# 1__Power.net
KiCad netlist of a schematic drawn in Altium Designer
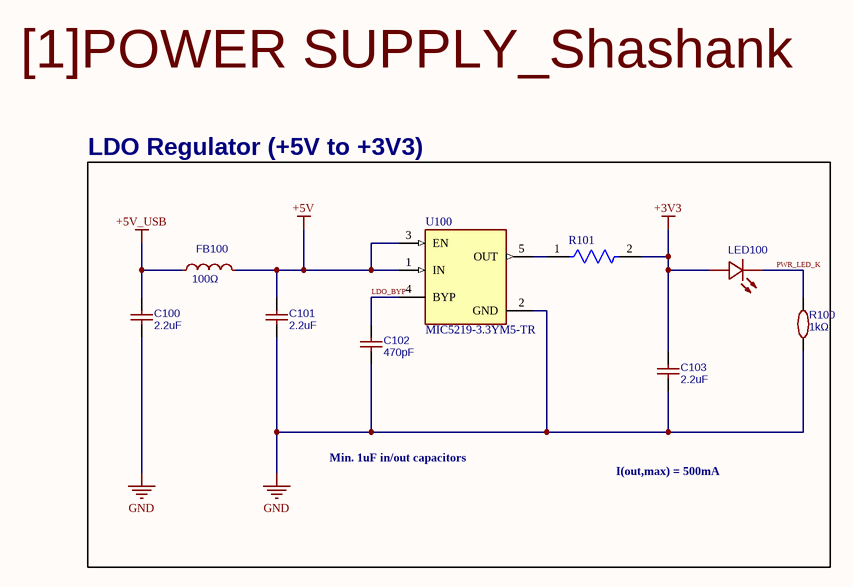
[diagram p0: [1]_Power.SchDoc]

(export (version "E")
  (design (tool "Eeschema 10.0.6"))
  (components
    (comp (ref "C100")
      (value "2.2uF")
      (footprint "C0603")
      (fields
        (field (name "MANUFACTURER PART") "CL10A225KO8NNNC")
        (field (name "MANUFACTURER") "SAMSUNG(三星)")
      )
      (libsource (lib "Power_Lib") (part "2.2uF"))
    )
    (comp (ref "C101")
      (value "2.2uF")
      (footprint "C0603")
      (fields
        (field (name "MANUFACTURER PART") "CL10A225KO8NNNC")
        (field (name "MANUFACTURER") "SAMSUNG(三星)")
      )
      (libsource (lib "Power_Lib") (part "2.2uF"))
    )
    (comp (ref "C102")
      (value "470pF")
      (footprint "C0402")
      (fields (field (name "MANUFACTURER") "FH(风华)") (field (name "MANUFACTURER PART") "0402B471K500NT"))
      (libsource (lib "Power_Lib") (part "470pF"))
    )
    (comp (ref "C103")
      (value "2.2uF")
      (footprint "C0603")
      (fields
        (field (name "MANUFACTURER PART") "CL10A225KO8NNNC")
        (field (name "MANUFACTURER") "SAMSUNG(三星)")
      )
      (libsource (lib "Power_Lib") (part "2.2uF"))
    )
    (comp (ref "FB100")
      (value "100Ω")
      (footprint "L0603")
      (fields
        (field (name "MANUFACTURER") "Sunlord(顺络)")
        (field (name "MANUFACTURER PART") "PZ1608D121-2R0TF")
      )
      (libsource (lib "Power_Lib") (part "120Ω"))
    )
    (comp (ref "LED100")
      (value "FC-F1005UGK-520M5")
      (footprint "LED0402-RD")
      (fields
        (field (name "MANUFACTURER") "国星光电")
        (field (name "MANUFACTURER PART") "NCD0402G1")
        (field (name "CONTRIBUTOR") "LCSC")
      )
      (libsource (lib "Power_Lib") (part "FC-F1005UGK-520M5"))
    )
    (comp (ref "R100")
      (value "1kΩ")
      (footprint "R0402")
      (fields
        (field (name "MANUFACTURER") "UNI-ROYAL(厚声)")
        (field (name "MANUFACTURER PART") "0402WGF1001TCE")
      )
      (libsource (lib "Power_Lib") (part "1kΩ"))
    )
    (comp (ref "R101")
      (value "CRCW04020000Z0ED")
      (footprint "FP-CRCW0402-e3-IPC_C")
      (description "RES Thick Film, 0Ω, 0.063W, 0402")
      (fields (field (name "TOLERANCE") "5%"))
      (libsource (lib "Altium Content Vault") (part "1029c3af85768c4190bb7ad29bc67b5"))
    )
    (comp (ref "U100")
      (value "MIC5219-3.3YM5-TR")
      (footprint "FP-SOT23-5LD-PL-1-IPC_C")
      (description "IC REG LINEAR 3.3V 500MA SOT23-5")
      (libsource (lib "Altium Content Vault") (part "16b36b16d6b7b40c29ab14718bc3058"))
    )
  )
  (nets
    (net (code "1") (name "+3V3") (class "Default")
      (node (ref "C103") (pin "2") (pinfunction "2_2") (pintype "passive"))
      (node (ref "LED100") (pin "2") (pinfunction "A_2") (pintype "passive"))
      (node (ref "R101") (pin "2") (pinfunction "2_2") (pintype "passive"))
    )
    (net (code "2") (name "+5V") (class "Default")
      (node (ref "C101") (pin "2") (pinfunction "2_2") (pintype "passive"))
      (node (ref "FB100") (pin "2") (pinfunction "2_2") (pintype "passive"))
      (node (ref "U100") (pin "1") (pinfunction "IN_1") (pintype "input"))
      (node (ref "U100") (pin "3") (pinfunction "EN_3") (pintype "input"))
    )
    (net (code "3") (name "+5V_USB") (class "Default")
      (node (ref "C100") (pin "2") (pinfunction "2_2") (pintype "passive"))
      (node (ref "FB100") (pin "1") (pinfunction "1_1") (pintype "passive"))
    )
    (net (code "4") (name "/LDO_BYP") (class "Default")
      (node (ref "C102") (pin "2") (pinfunction "2_2") (pintype "passive"))
      (node (ref "U100") (pin "4") (pinfunction "BYP_4") (pintype "passive"))
    )
    (net (code "5") (name "/PWR_LED_K") (class "Default")
      (node (ref "LED100") (pin "1") (pinfunction "K_1") (pintype "passive"))
      (node (ref "R100") (pin "2") (pinfunction "2_2") (pintype "passive"))
    )
    (net (code "6") (name "GND") (class "Default")
      (node (ref "C100") (pin "1") (pinfunction "1_1") (pintype "passive"))
      (node (ref "C101") (pin "1") (pinfunction "1_1") (pintype "passive"))
      (node (ref "C102") (pin "1") (pinfunction "1_1") (pintype "passive"))
      (node (ref "C103") (pin "1") (pinfunction "1_1") (pintype "passive"))
      (node (ref "R100") (pin "1") (pinfunction "1_1") (pintype "passive"))
      (node (ref "U100") (pin "2") (pinfunction "GND_2") (pintype "power_in"))
    )
    (net (code "7") (name "Net-(U100-OUT)") (class "Default")
      (node (ref "R101") (pin "1") (pinfunction "1_1") (pintype "passive"))
      (node (ref "U100") (pin "5") (pinfunction "OUT_5") (pintype "output"))
    )
  )
)
